# servocontrol.net
KiCad netlist of a schematic drawn in EAGLE
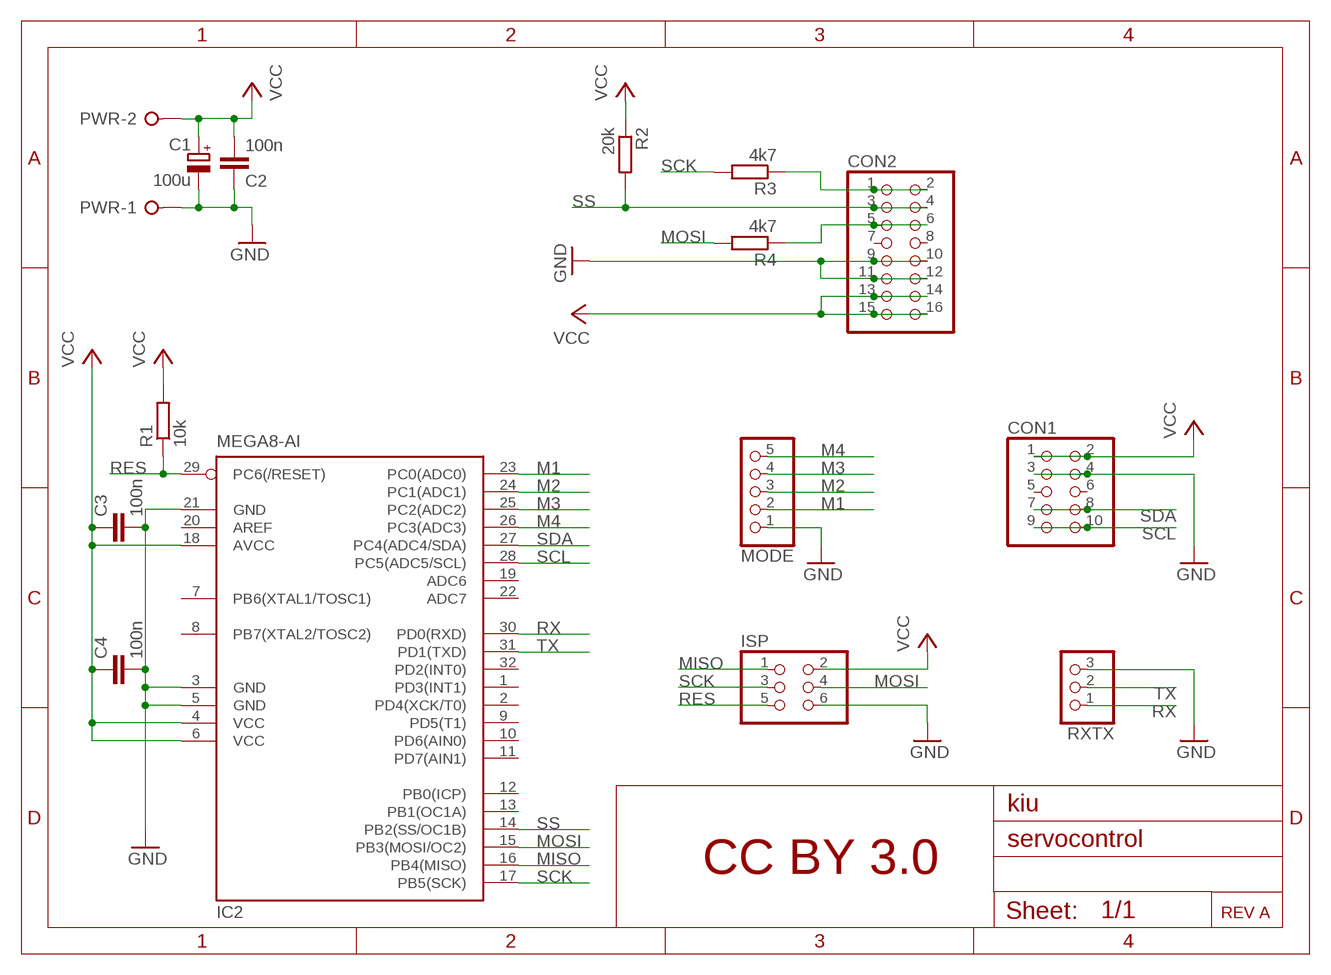
[diagram p0: schematic, sheet 1]

(export (version "E")
  (design (tool "Eeschema 10.0.6"))
  (components
    (comp (ref "C1")
      (value "100u")
      (footprint "eagle-import:153CLV-0505")
      (libsource (lib "eagle-import") (part "CPOL-EU153CLV-0505"))
    )
    (comp (ref "C2")
      (value "100n")
      (footprint "eagle-import:C0805")
      (libsource (lib "eagle-import") (part "C-EUC0805"))
    )
    (comp (ref "C3")
      (value "100n")
      (footprint "eagle-import:C0805")
      (libsource (lib "eagle-import") (part "C-EUC0805"))
    )
    (comp (ref "C4")
      (value "100n")
      (footprint "eagle-import:C0805")
      (libsource (lib "eagle-import") (part "C-EUC0805"))
    )
    (comp (ref "CON1")
      (value "PINHD-2X5")
      (footprint "eagle-import:2X05")
      (libsource (lib "eagle-import") (part "PINHD-2X5"))
    )
    (comp (ref "CON2")
      (value "PINHD-2X8")
      (footprint "eagle-import:2X08")
      (libsource (lib "eagle-import") (part "PINHD-2X8"))
    )
    (comp (ref "IC2")
      (value "MEGA8-AI")
      (footprint "eagle-import:TQFP32-08")
      (fields
        (field (name "MPN") "ATMEGA8-16AU")
        (field (name "MPN_1") "ATMEGA8-16AU")
        (field (name "OC_FARNELL") "9171371")
        (field (name "OC_NEWARK") "73M8863")
      )
      (libsource (lib "eagle-import") (part "MEGA8-AI"))
    )
    (comp (ref "ISP")
      (value "PINHD-2X3")
      (footprint "eagle-import:2X03")
      (libsource (lib "eagle-import") (part "PINHD-2X3"))
    )
    (comp (ref "MODE")
      (value "PINHD-1X5")
      (footprint "eagle-import:1X05")
      (libsource (lib "eagle-import") (part "PINHD-1X5"))
    )
    (comp (ref "PWR")
      (value "W237-02P")
      (footprint "eagle-import:W237-132")
      (libsource (lib "eagle-import") (part "W237-02P"))
    )
    (comp (ref "R1")
      (value "10k")
      (footprint "eagle-import:R0805")
      (libsource (lib "eagle-import") (part "R-EU_R0805"))
    )
    (comp (ref "R2")
      (value "20k")
      (footprint "eagle-import:R0805")
      (libsource (lib "eagle-import") (part "R-EU_R0805"))
    )
    (comp (ref "R3")
      (value "4k7")
      (footprint "eagle-import:R0805")
      (libsource (lib "eagle-import") (part "R-EU_R0805"))
    )
    (comp (ref "R4")
      (value "4k7")
      (footprint "eagle-import:R0805")
      (libsource (lib "eagle-import") (part "R-EU_R0805"))
    )
    (comp (ref "RXTX")
      (value "PINHD-1X3")
      (footprint "eagle-import:1X03")
      (libsource (lib "eagle-import") (part "PINHD-1X3"))
    )
  )
  (nets
    (net (code "1") (name "/M1") (class "Default")
      (node (ref "IC2") (pin "23") (pinfunction "PC0(ADC0)_23") (pintype "bidirectional"))
      (node (ref "MODE") (pin "2") (pinfunction "2_2") (pintype "passive"))
    )
    (net (code "2") (name "/M2") (class "Default")
      (node (ref "IC2") (pin "24") (pinfunction "PC1(ADC1)_24") (pintype "bidirectional"))
      (node (ref "MODE") (pin "3") (pinfunction "3_3") (pintype "passive"))
    )
    (net (code "3") (name "/M3") (class "Default")
      (node (ref "IC2") (pin "25") (pinfunction "PC2(ADC2)_25") (pintype "bidirectional"))
      (node (ref "MODE") (pin "4") (pinfunction "4_4") (pintype "passive"))
    )
    (net (code "4") (name "/M4") (class "Default")
      (node (ref "IC2") (pin "26") (pinfunction "PC3(ADC3)_26") (pintype "bidirectional"))
      (node (ref "MODE") (pin "5") (pinfunction "5_5") (pintype "passive"))
    )
    (net (code "5") (name "/MISO") (class "Default")
      (node (ref "IC2") (pin "16") (pinfunction "PB4(MISO)_16") (pintype "bidirectional"))
      (node (ref "ISP") (pin "1") (pinfunction "1_1") (pintype "passive"))
    )
    (net (code "6") (name "/MOSI") (class "Default")
      (node (ref "IC2") (pin "15") (pinfunction "PB3(MOSI/OC2)_15") (pintype "bidirectional"))
      (node (ref "ISP") (pin "4") (pinfunction "4_4") (pintype "passive"))
      (node (ref "R4") (pin "2") (pinfunction "2_2") (pintype "passive"))
    )
    (net (code "7") (name "/RES") (class "Default")
      (node (ref "IC2") (pin "29") (pinfunction "PC6(/RESET)_29") (pintype "bidirectional"))
      (node (ref "ISP") (pin "5") (pinfunction "5_5") (pintype "passive"))
      (node (ref "R1") (pin "1") (pinfunction "1_1") (pintype "passive"))
    )
    (net (code "8") (name "/RX") (class "Default")
      (node (ref "IC2") (pin "30") (pinfunction "PD0(RXD)_30") (pintype "bidirectional"))
      (node (ref "RXTX") (pin "1") (pinfunction "1_1") (pintype "passive"))
    )
    (net (code "9") (name "/SCK") (class "Default")
      (node (ref "IC2") (pin "17") (pinfunction "PB5(SCK)_17") (pintype "bidirectional"))
      (node (ref "ISP") (pin "3") (pinfunction "3_3") (pintype "passive"))
      (node (ref "R3") (pin "2") (pinfunction "2_2") (pintype "passive"))
    )
    (net (code "10") (name "/SCL") (class "Default")
      (node (ref "CON1") (pin "10") (pinfunction "10_10") (pintype "passive"))
      (node (ref "CON1") (pin "9") (pinfunction "9_9") (pintype "passive"))
      (node (ref "IC2") (pin "28") (pinfunction "PC5(ADC5/SCL)_28") (pintype "bidirectional"))
    )
    (net (code "11") (name "/SDA") (class "Default")
      (node (ref "CON1") (pin "7") (pinfunction "7_7") (pintype "passive"))
      (node (ref "CON1") (pin "8") (pinfunction "8_8") (pintype "passive"))
      (node (ref "IC2") (pin "27") (pinfunction "PC4(ADC4/SDA)_27") (pintype "bidirectional"))
    )
    (net (code "12") (name "/SS") (class "Default")
      (node (ref "CON2") (pin "3") (pinfunction "3_3") (pintype "passive"))
      (node (ref "CON2") (pin "4") (pinfunction "4_4") (pintype "passive"))
      (node (ref "IC2") (pin "14") (pinfunction "PB2(SS/OC1B)_14") (pintype "bidirectional"))
      (node (ref "R2") (pin "2") (pinfunction "2_2") (pintype "passive"))
    )
    (net (code "13") (name "/TX") (class "Default")
      (node (ref "IC2") (pin "31") (pinfunction "PD1(TXD)_31") (pintype "bidirectional"))
      (node (ref "RXTX") (pin "2") (pinfunction "2_2") (pintype "passive"))
    )
    (net (code "14") (name "GND") (class "Default")
      (node (ref "C1") (pin "-") (pinfunction "-_-") (pintype "passive"))
      (node (ref "C2") (pin "1") (pinfunction "1_1") (pintype "passive"))
      (node (ref "C3") (pin "2") (pinfunction "2_2") (pintype "passive"))
      (node (ref "C4") (pin "2") (pinfunction "2_2") (pintype "passive"))
      (node (ref "CON1") (pin "3") (pinfunction "3_3") (pintype "passive"))
      (node (ref "CON1") (pin "4") (pinfunction "4_4") (pintype "passive"))
      (node (ref "CON2") (pin "10") (pinfunction "10_10") (pintype "passive"))
      (node (ref "CON2") (pin "11") (pinfunction "11_11") (pintype "passive"))
      (node (ref "CON2") (pin "12") (pinfunction "12_12") (pintype "passive"))
      (node (ref "CON2") (pin "9") (pinfunction "9_9") (pintype "passive"))
      (node (ref "IC2") (pin "21") (pinfunction "GND_21") (pintype "power_in"))
      (node (ref "IC2") (pin "3") (pinfunction "GND_3") (pintype "power_in"))
      (node (ref "IC2") (pin "5") (pinfunction "GND_5") (pintype "power_in"))
      (node (ref "ISP") (pin "6") (pinfunction "6_6") (pintype "passive"))
      (node (ref "MODE") (pin "1") (pinfunction "1_1") (pintype "passive"))
      (node (ref "PWR") (pin "1") (pinfunction "KL_1") (pintype "passive"))
      (node (ref "RXTX") (pin "3") (pinfunction "3_3") (pintype "passive"))
    )
    (net (code "15") (name "Net-(CON2-Pad1)") (class "Default")
      (node (ref "CON2") (pin "1") (pinfunction "1_1") (pintype "passive"))
      (node (ref "CON2") (pin "2") (pinfunction "2_2") (pintype "passive"))
      (node (ref "R3") (pin "1") (pinfunction "1_1") (pintype "passive"))
    )
    (net (code "16") (name "Net-(CON2-Pad5)") (class "Default")
      (node (ref "CON2") (pin "5") (pinfunction "5_5") (pintype "passive"))
      (node (ref "CON2") (pin "6") (pinfunction "6_6") (pintype "passive"))
      (node (ref "R4") (pin "1") (pinfunction "1_1") (pintype "passive"))
    )
    (net (code "17") (name "VCC") (class "Default")
      (node (ref "C1") (pin "+") (pinfunction "+_+") (pintype "passive"))
      (node (ref "C2") (pin "2") (pinfunction "2_2") (pintype "passive"))
      (node (ref "C3") (pin "1") (pinfunction "1_1") (pintype "passive"))
      (node (ref "C4") (pin "1") (pinfunction "1_1") (pintype "passive"))
      (node (ref "CON1") (pin "1") (pinfunction "1_1") (pintype "passive"))
      (node (ref "CON1") (pin "2") (pinfunction "2_2") (pintype "passive"))
      (node (ref "CON2") (pin "13") (pinfunction "13_13") (pintype "passive"))
      (node (ref "CON2") (pin "14") (pinfunction "14_14") (pintype "passive"))
      (node (ref "CON2") (pin "15") (pinfunction "15_15") (pintype "passive"))
      (node (ref "CON2") (pin "16") (pinfunction "16_16") (pintype "passive"))
      (node (ref "IC2") (pin "18") (pinfunction "AVCC_18") (pintype "power_in"))
      (node (ref "IC2") (pin "4") (pinfunction "VCC_4") (pintype "power_in"))
      (node (ref "IC2") (pin "6") (pinfunction "VCC_6") (pintype "power_in"))
      (node (ref "ISP") (pin "2") (pinfunction "2_2") (pintype "passive"))
      (node (ref "PWR") (pin "2") (pinfunction "KL_2") (pintype "passive"))
      (node (ref "R1") (pin "2") (pinfunction "2_2") (pintype "passive"))
      (node (ref "R2") (pin "1") (pinfunction "1_1") (pintype "passive"))
    )
    (net (code "18") (name "unconnected-(CON1-Pad5)") (class "Default")
      (node (ref "CON1") (pin "5") (pinfunction "5_5") (pintype "passive"))
    )
    (net (code "19") (name "unconnected-(CON1-Pad6)") (class "Default")
      (node (ref "CON1") (pin "6") (pinfunction "6_6") (pintype "passive"))
    )
    (net (code "20") (name "unconnected-(CON2-Pad7)") (class "Default")
      (node (ref "CON2") (pin "7") (pinfunction "7_7") (pintype "passive"))
    )
    (net (code "21") (name "unconnected-(CON2-Pad8)") (class "Default")
      (node (ref "CON2") (pin "8") (pinfunction "8_8") (pintype "passive"))
    )
    (net (code "22") (name "unconnected-(IC2-ADC6-Pad19)") (class "Default")
      (node (ref "IC2") (pin "19") (pinfunction "ADC6_19") (pintype "bidirectional"))
    )
    (net (code "23") (name "unconnected-(IC2-ADC7-Pad22)") (class "Default")
      (node (ref "IC2") (pin "22") (pinfunction "ADC7_22") (pintype "bidirectional"))
    )
    (net (code "24") (name "unconnected-(IC2-AREF-Pad20)") (class "Default")
      (node (ref "IC2") (pin "20") (pinfunction "AREF_20") (pintype "passive"))
    )
    (net (code "25") (name "unconnected-(IC2-PB0(ICP)-Pad12)") (class "Default")
      (node (ref "IC2") (pin "12") (pinfunction "PB0(ICP)_12") (pintype "bidirectional"))
    )
    (net (code "26") (name "unconnected-(IC2-PB1(OC1A)-Pad13)") (class "Default")
      (node (ref "IC2") (pin "13") (pinfunction "PB1(OC1A)_13") (pintype "bidirectional"))
    )
    (net (code "27") (name "unconnected-(IC2-PB6(XTAL1{slash}TOSC1)-Pad7)") (class "Default")
      (node (ref "IC2") (pin "7") (pinfunction "PB6(XTAL1/TOSC1)_7") (pintype "bidirectional"))
    )
    (net (code "28") (name "unconnected-(IC2-PB7(XTAL2{slash}TOSC2)-Pad8)") (class "Default")
      (node (ref "IC2") (pin "8") (pinfunction "PB7(XTAL2/TOSC2)_8") (pintype "bidirectional"))
    )
    (net (code "29") (name "unconnected-(IC2-PD2(INT0)-Pad32)") (class "Default")
      (node (ref "IC2") (pin "32") (pinfunction "PD2(INT0)_32") (pintype "bidirectional"))
    )
    (net (code "30") (name "unconnected-(IC2-PD3(INT1)-Pad1)") (class "Default")
      (node (ref "IC2") (pin "1") (pinfunction "PD3(INT1)_1") (pintype "bidirectional"))
    )
    (net (code "31") (name "unconnected-(IC2-PD4(XCK{slash}T0)-Pad2)") (class "Default")
      (node (ref "IC2") (pin "2") (pinfunction "PD4(XCK/T0)_2") (pintype "bidirectional"))
    )
    (net (code "32") (name "unconnected-(IC2-PD5(T1)-Pad9)") (class "Default")
      (node (ref "IC2") (pin "9") (pinfunction "PD5(T1)_9") (pintype "bidirectional"))
    )
    (net (code "33") (name "unconnected-(IC2-PD6(AIN0)-Pad10)") (class "Default")
      (node (ref "IC2") (pin "10") (pinfunction "PD6(AIN0)_10") (pintype "bidirectional"))
    )
    (net (code "34") (name "unconnected-(IC2-PD7(AIN1)-Pad11)") (class "Default")
      (node (ref "IC2") (pin "11") (pinfunction "PD7(AIN1)_11") (pintype "bidirectional"))
    )
  )
)
